# Cascade.net
KiCad netlist of a schematic drawn in Altium Designer
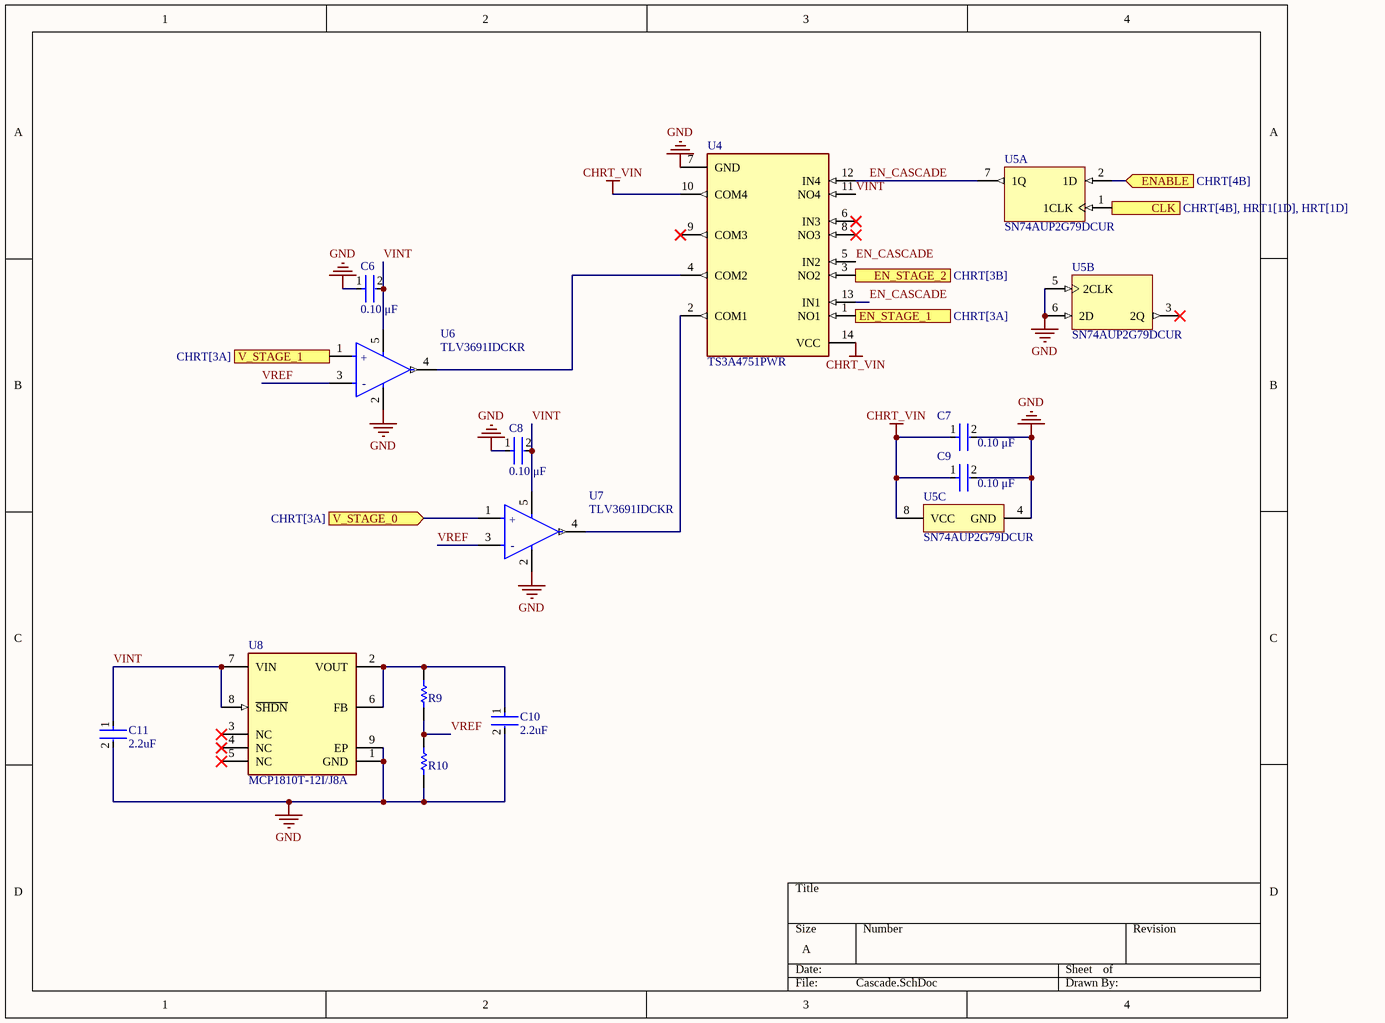
[diagram p0: Cascade.SchDoc]

(export (version "E")
  (design (tool "Eeschema 10.0.6"))
  (components
    (comp (ref "C6")
      (value "C0402C104K8PACTU")
      (footprint "FP-C0402-BB-MFG")
      (description "CAP CER 0.1UF 10V X5R 0402")
      (fields
        (field (name "CAPACITANCE") "0.10 μF")
        (field (name "MANUFACTURER") "Kemet")
        (field (name "TOLERANCE") "0.1")
      )
      (libsource (lib "Altium Content Vault") (part "b4654b650e69147ec39a6b967a45e02"))
    )
    (comp (ref "C7")
      (value "C0402C104K8PACTU")
      (footprint "FP-C0402-BB-MFG")
      (description "CAP CER 0.1UF 10V X5R 0402")
      (fields
        (field (name "CAPACITANCE") "0.10 μF")
        (field (name "MANUFACTURER") "Kemet")
        (field (name "TOLERANCE") "0.1")
      )
      (libsource (lib "Altium Content Vault") (part "b4654b650e69147ec39a6b967a45e02"))
    )
    (comp (ref "C8")
      (value "C0402C104K8PACTU")
      (footprint "FP-C0402-BB-MFG")
      (description "CAP CER 0.1UF 10V X5R 0402")
      (fields
        (field (name "CAPACITANCE") "0.10 μF")
        (field (name "MANUFACTURER") "Kemet")
        (field (name "TOLERANCE") "0.1")
      )
      (libsource (lib "Altium Content Vault") (part "b4654b650e69147ec39a6b967a45e02"))
    )
    (comp (ref "C9")
      (value "C0402C104K8PACTU")
      (footprint "FP-C0402-BB-MFG")
      (description "CAP CER 0.1UF 10V X5R 0402")
      (fields
        (field (name "CAPACITANCE") "0.10 μF")
        (field (name "MANUFACTURER") "Kemet")
        (field (name "TOLERANCE") "0.1")
      )
      (libsource (lib "Altium Content Vault") (part "b4654b650e69147ec39a6b967a45e02"))
    )
    (comp (ref "C10")
      (value "GRM188R71A225KE15D")
      (footprint "FP-GRM188-0_1-e0_2_0_5-MFG")
      (description "Chip Multilayer Ceramic Capacitors for General Purpose, 0603, 2.2uF, X7R, 15%, 10%, 10V")
      (fields
        (field (name "VOLTAGE") "10V")
        (field (name "CAPACITANCE") "2.2uF")
        (field (name "TOLERANCE") "10%")
      )
      (libsource (lib "Altium Content Vault") (part "11868f565c42a9108669ba33697ecf6"))
    )
    (comp (ref "C11")
      (value "GRM188R71A225KE15D")
      (footprint "FP-GRM188-0_1-e0_2_0_5-MFG")
      (description "Chip Multilayer Ceramic Capacitors for General Purpose, 0603, 2.2uF, X7R, 15%, 10%, 10V")
      (fields
        (field (name "VOLTAGE") "10V")
        (field (name "CAPACITANCE") "2.2uF")
        (field (name "TOLERANCE") "10%")
      )
      (libsource (lib "Altium Content Vault") (part "11868f565c42a9108669ba33697ecf6"))
    )
    (comp (ref "R9")
      (value "ERJ-2GEJ915X")
      (footprint "RESC1005X40X25LL05T05")
      (fields (field (name "MANUFACTURER") "Panasonic"))
      (libsource (lib "Altium Content Vault") (part "RES"))
    )
    (comp (ref "R10")
      (value "CRCW04022M40FKED")
      (footprint "RESC1005X40X25LL05T05")
      (fields (field (name "MANUFACTURER") "Vishay Dale"))
      (libsource (lib "Altium Content Vault") (part "RES"))
    )
    (comp (ref "U4")
      (value "TS3A4751PWR")
      (footprint "FP-PW0014A-IPC_C")
      (description "IC SWITCH QUAD SPST 14TSSOP")
      (libsource (lib "Altium Content Vault") (part "75fdcfb842d41a92b92a478e82e68ae"))
    )
    (comp (ref "U5")
      (value "SN74AUP2G79DCUR")
      (footprint "DCU0008A_L")
      (description "Low-Power Dual Positive-Edge-Triggered D-Type Flip-Flop, DCU0008A, LARGE T&R")
      (fields
        (field (name "MANUFACTURER") "Texas Instruments")
        (field (name "GENERIC PART NUMBER") "SN74AUP2G79")
      )
      (libsource (lib "") (part "TI-SN74XXX2G79-8_A_1"))
    )
    (comp (ref "U6")
      (value "TLV3691IDCKR")
      (footprint "FP-DCK0005A-IPC_A")
      (description "IC COMPARATOR NANO-POWER SC70-5")
      (libsource (lib "Altium Content Vault") (part "3dae5d43319efa9f60be5f7de20330d"))
    )
    (comp (ref "U7")
      (value "TLV3691IDCKR")
      (footprint "FP-DCK0005A-IPC_A")
      (description "IC COMPARATOR NANO-POWER SC70-5")
      (libsource (lib "Altium Content Vault") (part "3dae5d43319efa9f60be5f7de20330d"))
    )
    (comp (ref "U8")
      (value "MCP1810T-12I/J8A")
      (footprint "FP-C04-1207A-MFG")
      (description "IC REG LINEAR 1.2V 150MA 8VDFN")
      (fields
        (field (name "MANUFACTURER") "Microchip Technology")
        (field (name "OCTOPART") "https://octopart.com/mcp1810t-12i%2Fj8a-microchip-75615047")
      )
      (libsource (lib "Altium Content Vault") (part "9c464f695c2e69d33b93af79e311a43"))
    )
  )
  (nets
    (net (code "1") (name "/CLK") (class "Default")
      (node (ref "U5") (pin "1") (pinfunction "1CLK_1") (pintype "input"))
    )
    (net (code "2") (name "/ENABLE") (class "Default")
      (node (ref "U5") (pin "2") (pinfunction "1D_2") (pintype "input"))
    )
    (net (code "3") (name "/EN_CASCADE") (class "Default")
      (node (ref "U4") (pin "12") (pinfunction "IN4_12") (pintype "input"))
      (node (ref "U4") (pin "13") (pinfunction "IN1_13") (pintype "input"))
      (node (ref "U4") (pin "5") (pinfunction "IN2_5") (pintype "input"))
      (node (ref "U5") (pin "7") (pinfunction "1Q_7") (pintype "output"))
    )
    (net (code "4") (name "/EN_STAGE_1") (class "Default")
      (node (ref "U4") (pin "1") (pinfunction "NO1_1") (pintype "input"))
    )
    (net (code "5") (name "/EN_STAGE_2") (class "Default")
      (node (ref "U4") (pin "3") (pinfunction "NO2_3") (pintype "input"))
    )
    (net (code "6") (name "/VINT") (class "Default")
      (node (ref "C11") (pin "1") (pinfunction "1_1") (pintype "passive"))
      (node (ref "C6") (pin "2") (pinfunction "2_2") (pintype "passive"))
      (node (ref "C8") (pin "2") (pinfunction "2_2") (pintype "passive"))
      (node (ref "U4") (pin "11") (pinfunction "NO4_11") (pintype "input"))
      (node (ref "U6") (pin "5") (pinfunction "VCC_5") (pintype "power_in"))
      (node (ref "U7") (pin "5") (pinfunction "VCC_5") (pintype "power_in"))
      (node (ref "U8") (pin "7") (pinfunction "VIN_7") (pintype "power_in"))
      (node (ref "U8") (pin "8") (pinfunction "~{SHDN}_8") (pintype "input"))
    )
    (net (code "7") (name "/VREF") (class "Default")
      (node (ref "R10") (pin "1") (pinfunction "1_1") (pintype "passive"))
      (node (ref "R9") (pin "1") (pinfunction "1_1") (pintype "passive"))
      (node (ref "U6") (pin "3") (pinfunction "IN-_3") (pintype "tri_state"))
      (node (ref "U7") (pin "3") (pinfunction "IN-_3") (pintype "tri_state"))
    )
    (net (code "8") (name "/V_STAGE_0") (class "Default")
      (node (ref "U7") (pin "1") (pinfunction "IN+_1") (pintype "tri_state"))
    )
    (net (code "9") (name "/V_STAGE_1") (class "Default")
      (node (ref "U6") (pin "1") (pinfunction "IN+_1") (pintype "tri_state"))
    )
    (net (code "10") (name "CHRT_VIN") (class "Default")
      (node (ref "C7") (pin "1") (pinfunction "1_1") (pintype "passive"))
      (node (ref "C9") (pin "1") (pinfunction "1_1") (pintype "passive"))
      (node (ref "U4") (pin "10") (pinfunction "COM4_10") (pintype "output"))
      (node (ref "U4") (pin "14") (pinfunction "VCC_14") (pintype "power_in"))
      (node (ref "U5") (pin "8") (pinfunction "VCC_8") (pintype "power_in"))
    )
    (net (code "11") (name "GND") (class "Default")
      (node (ref "C10") (pin "2") (pinfunction "2_2") (pintype "passive"))
      (node (ref "C11") (pin "2") (pinfunction "2_2") (pintype "passive"))
      (node (ref "C6") (pin "1") (pinfunction "1_1") (pintype "passive"))
      (node (ref "C7") (pin "2") (pinfunction "2_2") (pintype "passive"))
      (node (ref "C8") (pin "1") (pinfunction "1_1") (pintype "passive"))
      (node (ref "C9") (pin "2") (pinfunction "2_2") (pintype "passive"))
      (node (ref "R10") (pin "2") (pinfunction "2_2") (pintype "passive"))
      (node (ref "U4") (pin "7") (pinfunction "GND_7") (pintype "power_in"))
      (node (ref "U5") (pin "4") (pinfunction "GND_4") (pintype "power_in"))
      (node (ref "U5") (pin "5") (pinfunction "2CLK_5") (pintype "input"))
      (node (ref "U5") (pin "6") (pinfunction "2D_6") (pintype "input"))
      (node (ref "U6") (pin "2") (pinfunction "GND_2") (pintype "power_in"))
      (node (ref "U7") (pin "2") (pinfunction "GND_2") (pintype "power_in"))
      (node (ref "U8") (pin "1") (pinfunction "GND_1") (pintype "power_in"))
      (node (ref "U8") (pin "9") (pinfunction "EP_9") (pintype "power_in"))
    )
    (net (code "12") (name "Net-(U4-COM1)") (class "Default")
      (node (ref "U4") (pin "2") (pinfunction "COM1_2") (pintype "output"))
      (node (ref "U7") (pin "4") (pinfunction "OUT_4") (pintype "output"))
    )
    (net (code "13") (name "Net-(U4-COM2)") (class "Default")
      (node (ref "U4") (pin "4") (pinfunction "COM2_4") (pintype "output"))
      (node (ref "U6") (pin "4") (pinfunction "OUT_4") (pintype "output"))
    )
    (net (code "14") (name "Net-(U8-FB)") (class "Default")
      (node (ref "C10") (pin "1") (pinfunction "1_1") (pintype "passive"))
      (node (ref "R9") (pin "2") (pinfunction "2_2") (pintype "passive"))
      (node (ref "U8") (pin "2") (pinfunction "VOUT_2") (pintype "power_in"))
      (node (ref "U8") (pin "6") (pinfunction "FB_6") (pintype "passive"))
    )
    (net (code "15") (name "unconnected-(U4-COM3-Pad9)") (class "Default")
      (node (ref "U4") (pin "9") (pinfunction "COM3_9") (pintype "output+no_connect"))
    )
    (net (code "16") (name "unconnected-(U4-IN3-Pad6)") (class "Default")
      (node (ref "U4") (pin "6") (pinfunction "IN3_6") (pintype "input+no_connect"))
    )
    (net (code "17") (name "unconnected-(U4-NO3-Pad8)") (class "Default")
      (node (ref "U4") (pin "8") (pinfunction "NO3_8") (pintype "input+no_connect"))
    )
    (net (code "18") (name "unconnected-(U5B-2Q-Pad3)") (class "Default")
      (node (ref "U5") (pin "3") (pinfunction "2Q_3") (pintype "output+no_connect"))
    )
    (net (code "19") (name "unconnected-(U8-NC-Pad3)") (class "Default")
      (node (ref "U8") (pin "3") (pinfunction "NC_3") (pintype "passive+no_connect"))
    )
    (net (code "20") (name "unconnected-(U8-NC-Pad4)") (class "Default")
      (node (ref "U8") (pin "4") (pinfunction "NC_4") (pintype "passive+no_connect"))
    )
    (net (code "21") (name "unconnected-(U8-NC-Pad5)") (class "Default")
      (node (ref "U8") (pin "5") (pinfunction "NC_5") (pintype "passive+no_connect"))
    )
  )
)
